# REG5V.net
KiCad netlist of a schematic drawn in Altium Designer
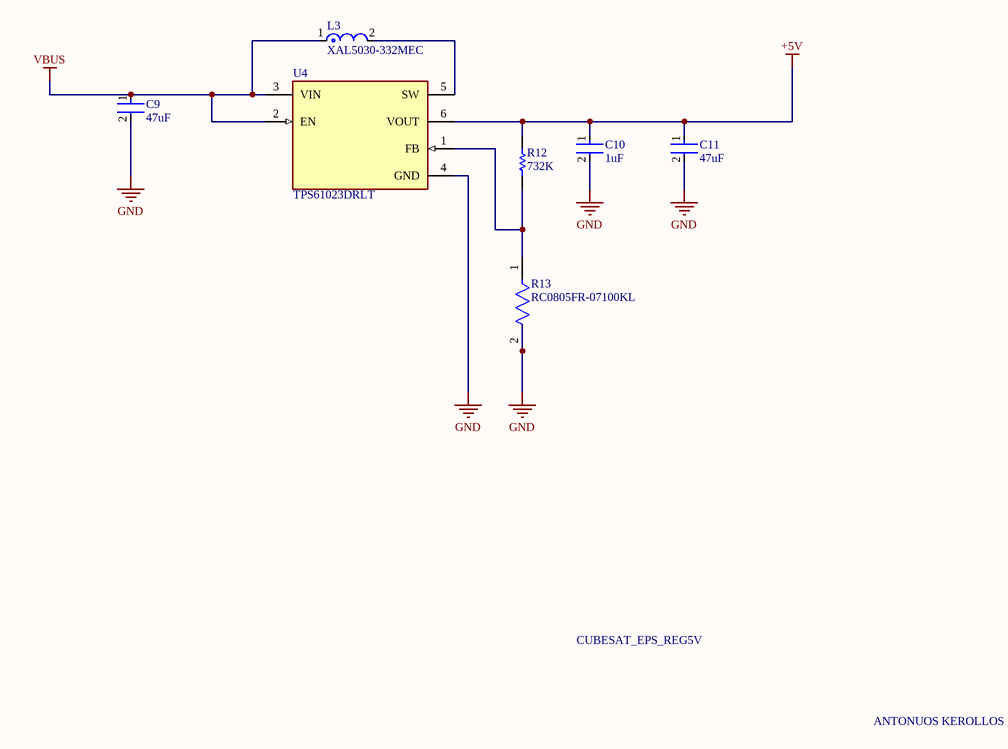
[diagram p0: REG5V.SchDoc]

(export (version "E")
  (design (tool "Eeschema 10.0.6"))
  (components
    (comp (ref "C9")
      (value "47uF")
      (footprint "FP-GRM32E-0_3-0_2-IPC_A")
      (description "Chip Multilayer Ceramic Capacitors for General Purpose, 1210, 47uF, X6S, 22%, 10%, 16V")
      (fields (field (name "VOLTAGE") "16V") (field (name "TOLERANCE") "10%"))
      (libsource (lib "Altium Content Vault") (part "02cd4be3c70576c341d710602a673aa"))
    )
    (comp (ref "C10")
      (value "1uF")
      (footprint "FP-CL10-IPC_B")
      (description "Cap Ceramic 1uF 10V X7R ±10% Pad SMD 0603 +125°C T/R")
      (fields (field (name "TOLERANCE") "10%"))
      (libsource (lib "Altium Content Vault") (part "b4654b650e69147ec39a6b967a45e02"))
    )
    (comp (ref "C11")
      (value "47uF")
      (footprint "FP-GRM32E-0_3-0_2-IPC_A")
      (description "Chip Multilayer Ceramic Capacitors for General Purpose, 1210, 47uF, X6S, 22%, 10%, 16V")
      (fields (field (name "VOLTAGE") "16V") (field (name "TOLERANCE") "10%"))
      (libsource (lib "Altium Content Vault") (part "02cd4be3c70576c341d710602a673aa"))
    )
    (comp (ref "L3")
      (value "XAL5030-332MEC")
      (footprint "FP-XAL5030-MFG")
      (description "Fixed Inductors 3.3uH Shld 20% 8.1A 23.3mOhms AECQ2")
      (fields (field (name "TOLERANCE") "20%"))
      (libsource (lib "Altium Content Vault") (part "4cc4b267dca4c8e51f7102f422741d8"))
    )
    (comp (ref "R12")
      (value "732K")
      (footprint "RESC2013X60X35ML10T20")
      (fields (field (name "MANUFACTURER") "Yageo") (field (name "PART NUMBER") "RC0805FR-07732KL"))
      (libsource (lib "Altium Content Vault") (part "RES"))
    )
    (comp (ref "R13")
      (value "RC0805FR-07100KL")
      (footprint "FP-RC0805-0_6-IPC_C")
      (description "RES 100K OHM 1% 1/8W 0805")
      (fields (field (name "TOLERANCE") "1%"))
      (libsource (lib "Altium Content Vault") (part "1029c3af85768c4190bb7ad29bc67b5"))
    )
    (comp (ref "U4")
      (value "TPS61023DRLT")
      (footprint "FP-DRL0006A-MFG")
      (description "IC REG BOOST ADJ 3A SOT563")
      (libsource (lib "Altium Content Vault") (part "18be21dd93a9c49e9e301f83ec69781"))
    )
  )
  (nets
    (net (code "1") (name "+5V") (class "Default")
      (node (ref "C10") (pin "1") (pinfunction "1_1") (pintype "passive"))
      (node (ref "C11") (pin "1") (pinfunction "1_1") (pintype "passive"))
      (node (ref "R12") (pin "1") (pinfunction "1_1") (pintype "passive"))
      (node (ref "U4") (pin "6") (pinfunction "VOUT_6") (pintype "power_in"))
    )
    (net (code "2") (name "GND") (class "Default")
      (node (ref "C10") (pin "2") (pinfunction "2_2") (pintype "passive"))
      (node (ref "C11") (pin "2") (pinfunction "2_2") (pintype "passive"))
      (node (ref "C9") (pin "2") (pinfunction "2_2") (pintype "passive"))
      (node (ref "R13") (pin "2") (pinfunction "2_2") (pintype "passive"))
      (node (ref "U4") (pin "4") (pinfunction "GND_4") (pintype "power_in"))
    )
    (net (code "3") (name "Net-(U4-FB)") (class "Default")
      (node (ref "R12") (pin "2") (pinfunction "2_2") (pintype "passive"))
      (node (ref "R13") (pin "1") (pinfunction "1_1") (pintype "passive"))
      (node (ref "U4") (pin "1") (pinfunction "FB_1") (pintype "input"))
    )
    (net (code "4") (name "Net-(U4-SW)") (class "Default")
      (node (ref "L3") (pin "2") (pinfunction "2_2") (pintype "passive"))
      (node (ref "U4") (pin "5") (pinfunction "SW_5") (pintype "passive"))
    )
    (net (code "5") (name "VBUS") (class "Default")
      (node (ref "C9") (pin "1") (pinfunction "1_1") (pintype "passive"))
      (node (ref "L3") (pin "1") (pinfunction "1_1") (pintype "passive"))
      (node (ref "U4") (pin "2") (pinfunction "EN_2") (pintype "input"))
      (node (ref "U4") (pin "3") (pinfunction "VIN_3") (pintype "power_in"))
    )
  )
)
